# WS2803_7segs_discrete-lightshield3.net
KiCad netlist of a schematic drawn in EAGLE
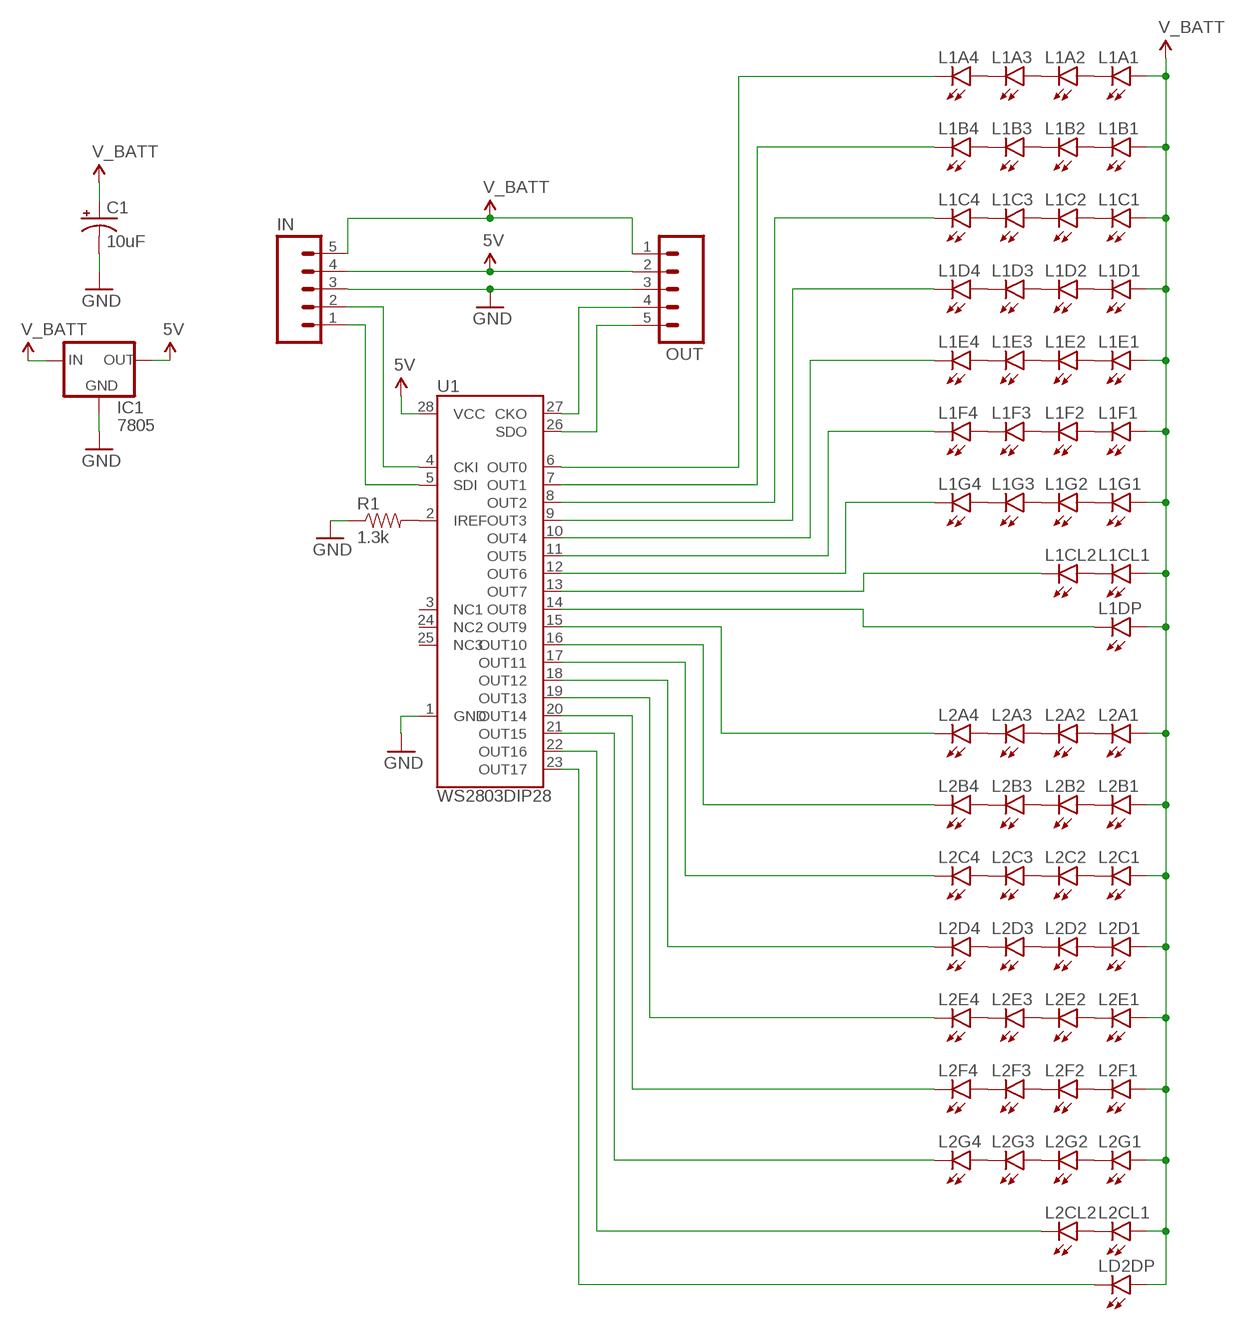
[diagram p0: schematic, sheet 1]

(export (version "E")
  (design (tool "Eeschema 10.0.6"))
  (components
    (comp (ref "C1")
      (value "10uF")
      (footprint "eagle-import:CPOL-RADIAL-10UF-25V")
      (libsource (lib "eagle-import") (part "CAP_POLPTH2"))
    )
    (comp (ref "IC1")
      (value "7805")
      (footprint "eagle-import:TO-92")
      (libsource (lib "eagle-import") (part "V_REG_78XXTO-92_FIXED"))
    )
    (comp (ref "IN")
      (value "M05PTH")
      (footprint "eagle-import:1X05")
      (libsource (lib "eagle-import") (part "M05PTH"))
    )
    (comp (ref "L1A1")
      (value "LED5MM")
      (footprint "eagle-import:LED5MM")
      (libsource (lib "eagle-import") (part "LED5MM"))
    )
    (comp (ref "L1A2")
      (value "LED5MM")
      (footprint "eagle-import:LED5MM")
      (libsource (lib "eagle-import") (part "LED5MM"))
    )
    (comp (ref "L1A3")
      (value "LED5MM")
      (footprint "eagle-import:LED5MM")
      (libsource (lib "eagle-import") (part "LED5MM"))
    )
    (comp (ref "L1A4")
      (value "LED5MM")
      (footprint "eagle-import:LED5MM")
      (libsource (lib "eagle-import") (part "LED5MM"))
    )
    (comp (ref "L1B1")
      (value "LED5MM")
      (footprint "eagle-import:LED5MM")
      (libsource (lib "eagle-import") (part "LED5MM"))
    )
    (comp (ref "L1B2")
      (value "LED5MM")
      (footprint "eagle-import:LED5MM")
      (libsource (lib "eagle-import") (part "LED5MM"))
    )
    (comp (ref "L1B3")
      (value "LED5MM")
      (footprint "eagle-import:LED5MM")
      (libsource (lib "eagle-import") (part "LED5MM"))
    )
    (comp (ref "L1B4")
      (value "LED5MM")
      (footprint "eagle-import:LED5MM")
      (libsource (lib "eagle-import") (part "LED5MM"))
    )
    (comp (ref "L1C1")
      (value "LED5MM")
      (footprint "eagle-import:LED5MM")
      (libsource (lib "eagle-import") (part "LED5MM"))
    )
    (comp (ref "L1C2")
      (value "LED5MM")
      (footprint "eagle-import:LED5MM")
      (libsource (lib "eagle-import") (part "LED5MM"))
    )
    (comp (ref "L1C3")
      (value "LED5MM")
      (footprint "eagle-import:LED5MM")
      (libsource (lib "eagle-import") (part "LED5MM"))
    )
    (comp (ref "L1C4")
      (value "LED5MM")
      (footprint "eagle-import:LED5MM")
      (libsource (lib "eagle-import") (part "LED5MM"))
    )
    (comp (ref "L1CL1")
      (value "LED5MM")
      (footprint "eagle-import:LED5MM")
      (libsource (lib "eagle-import") (part "LED5MM"))
    )
    (comp (ref "L1CL2")
      (value "LED5MM")
      (footprint "eagle-import:LED5MM")
      (libsource (lib "eagle-import") (part "LED5MM"))
    )
    (comp (ref "L1D1")
      (value "LED5MM")
      (footprint "eagle-import:LED5MM")
      (libsource (lib "eagle-import") (part "LED5MM"))
    )
    (comp (ref "L1D2")
      (value "LED5MM")
      (footprint "eagle-import:LED5MM")
      (libsource (lib "eagle-import") (part "LED5MM"))
    )
    (comp (ref "L1D3")
      (value "LED5MM")
      (footprint "eagle-import:LED5MM")
      (libsource (lib "eagle-import") (part "LED5MM"))
    )
    (comp (ref "L1D4")
      (value "LED5MM")
      (footprint "eagle-import:LED5MM")
      (libsource (lib "eagle-import") (part "LED5MM"))
    )
    (comp (ref "L1DP")
      (value "LED5MM")
      (footprint "eagle-import:LED5MM")
      (libsource (lib "eagle-import") (part "LED5MM"))
    )
    (comp (ref "L1E1")
      (value "LED5MM")
      (footprint "eagle-import:LED5MM")
      (libsource (lib "eagle-import") (part "LED5MM"))
    )
    (comp (ref "L1E2")
      (value "LED5MM")
      (footprint "eagle-import:LED5MM")
      (libsource (lib "eagle-import") (part "LED5MM"))
    )
    (comp (ref "L1E3")
      (value "LED5MM")
      (footprint "eagle-import:LED5MM")
      (libsource (lib "eagle-import") (part "LED5MM"))
    )
    (comp (ref "L1E4")
      (value "LED5MM")
      (footprint "eagle-import:LED5MM")
      (libsource (lib "eagle-import") (part "LED5MM"))
    )
    (comp (ref "L1F1")
      (value "LED5MM")
      (footprint "eagle-import:LED5MM")
      (libsource (lib "eagle-import") (part "LED5MM"))
    )
    (comp (ref "L1F2")
      (value "LED5MM")
      (footprint "eagle-import:LED5MM")
      (libsource (lib "eagle-import") (part "LED5MM"))
    )
    (comp (ref "L1F3")
      (value "LED5MM")
      (footprint "eagle-import:LED5MM")
      (libsource (lib "eagle-import") (part "LED5MM"))
    )
    (comp (ref "L1F4")
      (value "LED5MM")
      (footprint "eagle-import:LED5MM")
      (libsource (lib "eagle-import") (part "LED5MM"))
    )
    (comp (ref "L1G1")
      (value "LED5MM")
      (footprint "eagle-import:LED5MM")
      (libsource (lib "eagle-import") (part "LED5MM"))
    )
    (comp (ref "L1G2")
      (value "LED5MM")
      (footprint "eagle-import:LED5MM")
      (libsource (lib "eagle-import") (part "LED5MM"))
    )
    (comp (ref "L1G3")
      (value "LED5MM")
      (footprint "eagle-import:LED5MM")
      (libsource (lib "eagle-import") (part "LED5MM"))
    )
    (comp (ref "L1G4")
      (value "LED5MM")
      (footprint "eagle-import:LED5MM")
      (libsource (lib "eagle-import") (part "LED5MM"))
    )
    (comp (ref "L2A1")
      (value "LED5MM")
      (footprint "eagle-import:LED5MM")
      (libsource (lib "eagle-import") (part "LED5MM"))
    )
    (comp (ref "L2A2")
      (value "LED5MM")
      (footprint "eagle-import:LED5MM")
      (libsource (lib "eagle-import") (part "LED5MM"))
    )
    (comp (ref "L2A3")
      (value "LED5MM")
      (footprint "eagle-import:LED5MM")
      (libsource (lib "eagle-import") (part "LED5MM"))
    )
    (comp (ref "L2A4")
      (value "LED5MM")
      (footprint "eagle-import:LED5MM")
      (libsource (lib "eagle-import") (part "LED5MM"))
    )
    (comp (ref "L2B1")
      (value "LED5MM")
      (footprint "eagle-import:LED5MM")
      (libsource (lib "eagle-import") (part "LED5MM"))
    )
    (comp (ref "L2B2")
      (value "LED5MM")
      (footprint "eagle-import:LED5MM")
      (libsource (lib "eagle-import") (part "LED5MM"))
    )
    (comp (ref "L2B3")
      (value "LED5MM")
      (footprint "eagle-import:LED5MM")
      (libsource (lib "eagle-import") (part "LED5MM"))
    )
    (comp (ref "L2B4")
      (value "LED5MM")
      (footprint "eagle-import:LED5MM")
      (libsource (lib "eagle-import") (part "LED5MM"))
    )
    (comp (ref "L2C1")
      (value "LED5MM")
      (footprint "eagle-import:LED5MM")
      (libsource (lib "eagle-import") (part "LED5MM"))
    )
    (comp (ref "L2C2")
      (value "LED5MM")
      (footprint "eagle-import:LED5MM")
      (libsource (lib "eagle-import") (part "LED5MM"))
    )
    (comp (ref "L2C3")
      (value "LED5MM")
      (footprint "eagle-import:LED5MM")
      (libsource (lib "eagle-import") (part "LED5MM"))
    )
    (comp (ref "L2C4")
      (value "LED5MM")
      (footprint "eagle-import:LED5MM")
      (libsource (lib "eagle-import") (part "LED5MM"))
    )
    (comp (ref "L2CL1")
      (value "LED5MM")
      (footprint "eagle-import:LED5MM")
      (libsource (lib "eagle-import") (part "LED5MM"))
    )
    (comp (ref "L2CL2")
      (value "LED5MM")
      (footprint "eagle-import:LED5MM")
      (libsource (lib "eagle-import") (part "LED5MM"))
    )
    (comp (ref "L2D1")
      (value "LED5MM")
      (footprint "eagle-import:LED5MM")
      (libsource (lib "eagle-import") (part "LED5MM"))
    )
    (comp (ref "L2D2")
      (value "LED5MM")
      (footprint "eagle-import:LED5MM")
      (libsource (lib "eagle-import") (part "LED5MM"))
    )
    (comp (ref "L2D3")
      (value "LED5MM")
      (footprint "eagle-import:LED5MM")
      (libsource (lib "eagle-import") (part "LED5MM"))
    )
    (comp (ref "L2D4")
      (value "LED5MM")
      (footprint "eagle-import:LED5MM")
      (libsource (lib "eagle-import") (part "LED5MM"))
    )
    (comp (ref "L2E1")
      (value "LED5MM")
      (footprint "eagle-import:LED5MM")
      (libsource (lib "eagle-import") (part "LED5MM"))
    )
    (comp (ref "L2E2")
      (value "LED5MM")
      (footprint "eagle-import:LED5MM")
      (libsource (lib "eagle-import") (part "LED5MM"))
    )
    (comp (ref "L2E3")
      (value "LED5MM")
      (footprint "eagle-import:LED5MM")
      (libsource (lib "eagle-import") (part "LED5MM"))
    )
    (comp (ref "L2E4")
      (value "LED5MM")
      (footprint "eagle-import:LED5MM")
      (libsource (lib "eagle-import") (part "LED5MM"))
    )
    (comp (ref "L2F1")
      (value "LED5MM")
      (footprint "eagle-import:LED5MM")
      (libsource (lib "eagle-import") (part "LED5MM"))
    )
    (comp (ref "L2F2")
      (value "LED5MM")
      (footprint "eagle-import:LED5MM")
      (libsource (lib "eagle-import") (part "LED5MM"))
    )
    (comp (ref "L2F3")
      (value "LED5MM")
      (footprint "eagle-import:LED5MM")
      (libsource (lib "eagle-import") (part "LED5MM"))
    )
    (comp (ref "L2F4")
      (value "LED5MM")
      (footprint "eagle-import:LED5MM")
      (libsource (lib "eagle-import") (part "LED5MM"))
    )
    (comp (ref "L2G1")
      (value "LED5MM")
      (footprint "eagle-import:LED5MM")
      (libsource (lib "eagle-import") (part "LED5MM"))
    )
    (comp (ref "L2G2")
      (value "LED5MM")
      (footprint "eagle-import:LED5MM")
      (libsource (lib "eagle-import") (part "LED5MM"))
    )
    (comp (ref "L2G3")
      (value "LED5MM")
      (footprint "eagle-import:LED5MM")
      (libsource (lib "eagle-import") (part "LED5MM"))
    )
    (comp (ref "L2G4")
      (value "LED5MM")
      (footprint "eagle-import:LED5MM")
      (libsource (lib "eagle-import") (part "LED5MM"))
    )
    (comp (ref "LD2DP")
      (value "LED5MM")
      (footprint "eagle-import:LED5MM")
      (libsource (lib "eagle-import") (part "LED5MM"))
    )
    (comp (ref "OUT")
      (value "M05PTH")
      (footprint "eagle-import:1X05")
      (libsource (lib "eagle-import") (part "M05PTH"))
    )
    (comp (ref "R1")
      (value "1.3k")
      (footprint "eagle-import:AXIAL-0.4")
      (libsource (lib "eagle-import") (part "RESISTORPTH-1/4W"))
    )
    (comp (ref "U1")
      (value "WS2803DIP28")
      (footprint "eagle-import:DIP28")
      (libsource (lib "eagle-import") (part "WS2803DIP28"))
    )
  )
  (nets
    (net (code "1") (name "5V") (class "Default")
      (node (ref "IC1") (pin "1") (pinfunction "OUT_1") (pintype "output"))
      (node (ref "IN") (pin "4") (pinfunction "4_4") (pintype "passive"))
      (node (ref "OUT") (pin "2") (pinfunction "2_2") (pintype "passive"))
      (node (ref "U1") (pin "28") (pinfunction "VCC_28") (pintype "bidirectional"))
    )
    (net (code "2") (name "GND") (class "Default")
      (node (ref "C1") (pin "2") (pinfunction "-_2") (pintype "passive"))
      (node (ref "IC1") (pin "2") (pinfunction "GND_2") (pintype "input"))
      (node (ref "IN") (pin "3") (pinfunction "3_3") (pintype "passive"))
      (node (ref "OUT") (pin "3") (pinfunction "3_3") (pintype "passive"))
      (node (ref "R1") (pin "P$1") (pinfunction "1_P$1") (pintype "passive"))
      (node (ref "U1") (pin "1") (pinfunction "GND_1") (pintype "bidirectional"))
    )
    (net (code "3") (name "Net-(L1A1-C)") (class "Default")
      (node (ref "L1A1") (pin "K") (pinfunction "C_K") (pintype "passive"))
      (node (ref "L1A2") (pin "A") (pinfunction "A_A") (pintype "passive"))
    )
    (net (code "4") (name "Net-(L1A2-C)") (class "Default")
      (node (ref "L1A2") (pin "K") (pinfunction "C_K") (pintype "passive"))
      (node (ref "L1A3") (pin "A") (pinfunction "A_A") (pintype "passive"))
    )
    (net (code "5") (name "Net-(L1A3-C)") (class "Default")
      (node (ref "L1A3") (pin "K") (pinfunction "C_K") (pintype "passive"))
      (node (ref "L1A4") (pin "A") (pinfunction "A_A") (pintype "passive"))
    )
    (net (code "6") (name "Net-(L1A4-C)") (class "Default")
      (node (ref "L1A4") (pin "K") (pinfunction "C_K") (pintype "passive"))
      (node (ref "U1") (pin "6") (pinfunction "OUT0_6") (pintype "bidirectional"))
    )
    (net (code "7") (name "Net-(L1B1-C)") (class "Default")
      (node (ref "L1B1") (pin "K") (pinfunction "C_K") (pintype "passive"))
      (node (ref "L1B2") (pin "A") (pinfunction "A_A") (pintype "passive"))
    )
    (net (code "8") (name "Net-(L1B2-C)") (class "Default")
      (node (ref "L1B2") (pin "K") (pinfunction "C_K") (pintype "passive"))
      (node (ref "L1B3") (pin "A") (pinfunction "A_A") (pintype "passive"))
    )
    (net (code "9") (name "Net-(L1B3-C)") (class "Default")
      (node (ref "L1B3") (pin "K") (pinfunction "C_K") (pintype "passive"))
      (node (ref "L1B4") (pin "A") (pinfunction "A_A") (pintype "passive"))
    )
    (net (code "10") (name "Net-(L1B4-C)") (class "Default")
      (node (ref "L1B4") (pin "K") (pinfunction "C_K") (pintype "passive"))
      (node (ref "U1") (pin "7") (pinfunction "OUT1_7") (pintype "bidirectional"))
    )
    (net (code "11") (name "Net-(L1C1-C)") (class "Default")
      (node (ref "L1C1") (pin "K") (pinfunction "C_K") (pintype "passive"))
      (node (ref "L1C2") (pin "A") (pinfunction "A_A") (pintype "passive"))
    )
    (net (code "12") (name "Net-(L1C2-C)") (class "Default")
      (node (ref "L1C2") (pin "K") (pinfunction "C_K") (pintype "passive"))
      (node (ref "L1C3") (pin "A") (pinfunction "A_A") (pintype "passive"))
    )
    (net (code "13") (name "Net-(L1C3-C)") (class "Default")
      (node (ref "L1C3") (pin "K") (pinfunction "C_K") (pintype "passive"))
      (node (ref "L1C4") (pin "A") (pinfunction "A_A") (pintype "passive"))
    )
    (net (code "14") (name "Net-(L1C4-C)") (class "Default")
      (node (ref "L1C4") (pin "K") (pinfunction "C_K") (pintype "passive"))
      (node (ref "U1") (pin "8") (pinfunction "OUT2_8") (pintype "bidirectional"))
    )
    (net (code "15") (name "Net-(L1CL1-C)") (class "Default")
      (node (ref "L1CL1") (pin "K") (pinfunction "C_K") (pintype "passive"))
      (node (ref "L1CL2") (pin "A") (pinfunction "A_A") (pintype "passive"))
    )
    (net (code "16") (name "Net-(L1CL2-C)") (class "Default")
      (node (ref "L1CL2") (pin "K") (pinfunction "C_K") (pintype "passive"))
      (node (ref "U1") (pin "13") (pinfunction "OUT7_13") (pintype "bidirectional"))
    )
    (net (code "17") (name "Net-(L1D1-C)") (class "Default")
      (node (ref "L1D1") (pin "K") (pinfunction "C_K") (pintype "passive"))
      (node (ref "L1D2") (pin "A") (pinfunction "A_A") (pintype "passive"))
    )
    (net (code "18") (name "Net-(L1D2-C)") (class "Default")
      (node (ref "L1D2") (pin "K") (pinfunction "C_K") (pintype "passive"))
      (node (ref "L1D3") (pin "A") (pinfunction "A_A") (pintype "passive"))
    )
    (net (code "19") (name "Net-(L1D3-C)") (class "Default")
      (node (ref "L1D3") (pin "K") (pinfunction "C_K") (pintype "passive"))
      (node (ref "L1D4") (pin "A") (pinfunction "A_A") (pintype "passive"))
    )
    (net (code "20") (name "Net-(L1D4-C)") (class "Default")
      (node (ref "L1D4") (pin "K") (pinfunction "C_K") (pintype "passive"))
      (node (ref "U1") (pin "9") (pinfunction "OUT3_9") (pintype "bidirectional"))
    )
    (net (code "21") (name "Net-(L1DP-C)") (class "Default")
      (node (ref "L1DP") (pin "K") (pinfunction "C_K") (pintype "passive"))
      (node (ref "U1") (pin "14") (pinfunction "OUT8_14") (pintype "bidirectional"))
    )
    (net (code "22") (name "Net-(L1E1-C)") (class "Default")
      (node (ref "L1E1") (pin "K") (pinfunction "C_K") (pintype "passive"))
      (node (ref "L1E2") (pin "A") (pinfunction "A_A") (pintype "passive"))
    )
    (net (code "23") (name "Net-(L1E2-C)") (class "Default")
      (node (ref "L1E2") (pin "K") (pinfunction "C_K") (pintype "passive"))
      (node (ref "L1E3") (pin "A") (pinfunction "A_A") (pintype "passive"))
    )
    (net (code "24") (name "Net-(L1E3-C)") (class "Default")
      (node (ref "L1E3") (pin "K") (pinfunction "C_K") (pintype "passive"))
      (node (ref "L1E4") (pin "A") (pinfunction "A_A") (pintype "passive"))
    )
    (net (code "25") (name "Net-(L1E4-C)") (class "Default")
      (node (ref "L1E4") (pin "K") (pinfunction "C_K") (pintype "passive"))
      (node (ref "U1") (pin "10") (pinfunction "OUT4_10") (pintype "bidirectional"))
    )
    (net (code "26") (name "Net-(L1F1-C)") (class "Default")
      (node (ref "L1F1") (pin "K") (pinfunction "C_K") (pintype "passive"))
      (node (ref "L1F2") (pin "A") (pinfunction "A_A") (pintype "passive"))
    )
    (net (code "27") (name "Net-(L1F2-C)") (class "Default")
      (node (ref "L1F2") (pin "K") (pinfunction "C_K") (pintype "passive"))
      (node (ref "L1F3") (pin "A") (pinfunction "A_A") (pintype "passive"))
    )
    (net (code "28") (name "Net-(L1F3-C)") (class "Default")
      (node (ref "L1F3") (pin "K") (pinfunction "C_K") (pintype "passive"))
      (node (ref "L1F4") (pin "A") (pinfunction "A_A") (pintype "passive"))
    )
    (net (code "29") (name "Net-(L1F4-C)") (class "Default")
      (node (ref "L1F4") (pin "K") (pinfunction "C_K") (pintype "passive"))
      (node (ref "U1") (pin "11") (pinfunction "OUT5_11") (pintype "bidirectional"))
    )
    (net (code "30") (name "Net-(L1G1-C)") (class "Default")
      (node (ref "L1G1") (pin "K") (pinfunction "C_K") (pintype "passive"))
      (node (ref "L1G2") (pin "A") (pinfunction "A_A") (pintype "passive"))
    )
    (net (code "31") (name "Net-(L1G2-C)") (class "Default")
      (node (ref "L1G2") (pin "K") (pinfunction "C_K") (pintype "passive"))
      (node (ref "L1G3") (pin "A") (pinfunction "A_A") (pintype "passive"))
    )
    (net (code "32") (name "Net-(L1G3-C)") (class "Default")
      (node (ref "L1G3") (pin "K") (pinfunction "C_K") (pintype "passive"))
      (node (ref "L1G4") (pin "A") (pinfunction "A_A") (pintype "passive"))
    )
    (net (code "33") (name "Net-(L1G4-C)") (class "Default")
      (node (ref "L1G4") (pin "K") (pinfunction "C_K") (pintype "passive"))
      (node (ref "U1") (pin "12") (pinfunction "OUT6_12") (pintype "bidirectional"))
    )
    (net (code "34") (name "Net-(L2A1-C)") (class "Default")
      (node (ref "L2A1") (pin "K") (pinfunction "C_K") (pintype "passive"))
      (node (ref "L2A2") (pin "A") (pinfunction "A_A") (pintype "passive"))
    )
    (net (code "35") (name "Net-(L2A2-C)") (class "Default")
      (node (ref "L2A2") (pin "K") (pinfunction "C_K") (pintype "passive"))
      (node (ref "L2A3") (pin "A") (pinfunction "A_A") (pintype "passive"))
    )
    (net (code "36") (name "Net-(L2A3-C)") (class "Default")
      (node (ref "L2A3") (pin "K") (pinfunction "C_K") (pintype "passive"))
      (node (ref "L2A4") (pin "A") (pinfunction "A_A") (pintype "passive"))
    )
    (net (code "37") (name "Net-(L2A4-C)") (class "Default")
      (node (ref "L2A4") (pin "K") (pinfunction "C_K") (pintype "passive"))
      (node (ref "U1") (pin "15") (pinfunction "OUT9_15") (pintype "bidirectional"))
    )
    (net (code "38") (name "Net-(L2B1-C)") (class "Default")
      (node (ref "L2B1") (pin "K") (pinfunction "C_K") (pintype "passive"))
      (node (ref "L2B2") (pin "A") (pinfunction "A_A") (pintype "passive"))
    )
    (net (code "39") (name "Net-(L2B2-C)") (class "Default")
      (node (ref "L2B2") (pin "K") (pinfunction "C_K") (pintype "passive"))
      (node (ref "L2B3") (pin "A") (pinfunction "A_A") (pintype "passive"))
    )
    (net (code "40") (name "Net-(L2B3-C)") (class "Default")
      (node (ref "L2B3") (pin "K") (pinfunction "C_K") (pintype "passive"))
      (node (ref "L2B4") (pin "A") (pinfunction "A_A") (pintype "passive"))
    )
    (net (code "41") (name "Net-(L2B4-C)") (class "Default")
      (node (ref "L2B4") (pin "K") (pinfunction "C_K") (pintype "passive"))
      (node (ref "U1") (pin "16") (pinfunction "OUT10_16") (pintype "bidirectional"))
    )
    (net (code "42") (name "Net-(L2C1-C)") (class "Default")
      (node (ref "L2C1") (pin "K") (pinfunction "C_K") (pintype "passive"))
      (node (ref "L2C2") (pin "A") (pinfunction "A_A") (pintype "passive"))
    )
    (net (code "43") (name "Net-(L2C2-C)") (class "Default")
      (node (ref "L2C2") (pin "K") (pinfunction "C_K") (pintype "passive"))
      (node (ref "L2C3") (pin "A") (pinfunction "A_A") (pintype "passive"))
    )
    (net (code "44") (name "Net-(L2C3-C)") (class "Default")
      (node (ref "L2C3") (pin "K") (pinfunction "C_K") (pintype "passive"))
      (node (ref "L2C4") (pin "A") (pinfunction "A_A") (pintype "passive"))
    )
    (net (code "45") (name "Net-(L2C4-C)") (class "Default")
      (node (ref "L2C4") (pin "K") (pinfunction "C_K") (pintype "passive"))
      (node (ref "U1") (pin "17") (pinfunction "OUT11_17") (pintype "bidirectional"))
    )
    (net (code "46") (name "Net-(L2CL1-C)") (class "Default")
      (node (ref "L2CL1") (pin "K") (pinfunction "C_K") (pintype "passive"))
      (node (ref "L2CL2") (pin "A") (pinfunction "A_A") (pintype "passive"))
    )
    (net (code "47") (name "Net-(L2CL2-C)") (class "Default")
      (node (ref "L2CL2") (pin "K") (pinfunction "C_K") (pintype "passive"))
      (node (ref "U1") (pin "22") (pinfunction "OUT16_22") (pintype "bidirectional"))
    )
    (net (code "48") (name "Net-(L2D1-C)") (class "Default")
      (node (ref "L2D1") (pin "K") (pinfunction "C_K") (pintype "passive"))
      (node (ref "L2D2") (pin "A") (pinfunction "A_A") (pintype "passive"))
    )
    (net (code "49") (name "Net-(L2D2-C)") (class "Default")
      (node (ref "L2D2") (pin "K") (pinfunction "C_K") (pintype "passive"))
      (node (ref "L2D3") (pin "A") (pinfunction "A_A") (pintype "passive"))
    )
    (net (code "50") (name "Net-(L2D3-C)") (class "Default")
      (node (ref "L2D3") (pin "K") (pinfunction "C_K") (pintype "passive"))
      (node (ref "L2D4") (pin "A") (pinfunction "A_A") (pintype "passive"))
    )
    (net (code "51") (name "Net-(L2D4-C)") (class "Default")
      (node (ref "L2D4") (pin "K") (pinfunction "C_K") (pintype "passive"))
      (node (ref "U1") (pin "18") (pinfunction "OUT12_18") (pintype "bidirectional"))
    )
    (net (code "52") (name "Net-(L2E1-C)") (class "Default")
      (node (ref "L2E1") (pin "K") (pinfunction "C_K") (pintype "passive"))
      (node (ref "L2E2") (pin "A") (pinfunction "A_A") (pintype "passive"))
    )
    (net (code "53") (name "Net-(L2E2-C)") (class "Default")
      (node (ref "L2E2") (pin "K") (pinfunction "C_K") (pintype "passive"))
      (node (ref "L2E3") (pin "A") (pinfunction "A_A") (pintype "passive"))
    )
    (net (code "54") (name "Net-(L2E3-C)") (class "Default")
      (node (ref "L2E3") (pin "K") (pinfunction "C_K") (pintype "passive"))
      (node (ref "L2E4") (pin "A") (pinfunction "A_A") (pintype "passive"))
    )
    (net (code "55") (name "Net-(L2E4-C)") (class "Default")
      (node (ref "L2E4") (pin "K") (pinfunction "C_K") (pintype "passive"))
      (node (ref "U1") (pin "19") (pinfunction "OUT13_19") (pintype "bidirectional"))
    )
    (net (code "56") (name "Net-(L2F1-C)") (class "Default")
      (node (ref "L2F1") (pin "K") (pinfunction "C_K") (pintype "passive"))
      (node (ref "L2F2") (pin "A") (pinfunction "A_A") (pintype "passive"))
    )
    (net (code "57") (name "Net-(L2F2-C)") (class "Default")
      (node (ref "L2F2") (pin "K") (pinfunction "C_K") (pintype "passive"))
      (node (ref "L2F3") (pin "A") (pinfunction "A_A") (pintype "passive"))
    )
    (net (code "58") (name "Net-(L2F3-C)") (class "Default")
      (node (ref "L2F3") (pin "K") (pinfunction "C_K") (pintype "passive"))
      (node (ref "L2F4") (pin "A") (pinfunction "A_A") (pintype "passive"))
    )
    (net (code "59") (name "Net-(L2F4-C)") (class "Default")
      (node (ref "L2F4") (pin "K") (pinfunction "C_K") (pintype "passive"))
      (node (ref "U1") (pin "20") (pinfunction "OUT14_20") (pintype "bidirectional"))
    )
    (net (code "60") (name "Net-(L2G1-C)") (class "Default")
      (node (ref "L2G1") (pin "K") (pinfunction "C_K") (pintype "passive"))
      (node (ref "L2G2") (pin "A") (pinfunction "A_A") (pintype "passive"))
    )
    (net (code "61") (name "Net-(L2G2-C)") (class "Default")
      (node (ref "L2G2") (pin "K") (pinfunction "C_K") (pintype "passive"))
      (node (ref "L2G3") (pin "A") (pinfunction "A_A") (pintype "passive"))
    )
    (net (code "62") (name "Net-(L2G3-C)") (class "Default")
      (node (ref "L2G3") (pin "K") (pinfunction "C_K") (pintype "passive"))
      (node (ref "L2G4") (pin "A") (pinfunction "A_A") (pintype "passive"))
    )
    (net (code "63") (name "Net-(L2G4-C)") (class "Default")
      (node (ref "L2G4") (pin "K") (pinfunction "C_K") (pintype "passive"))
      (node (ref "U1") (pin "21") (pinfunction "OUT15_21") (pintype "bidirectional"))
    )
    (net (code "64") (name "Net-(LD2DP-C)") (class "Default")
      (node (ref "LD2DP") (pin "K") (pinfunction "C_K") (pintype "passive"))
      (node (ref "U1") (pin "23") (pinfunction "OUT17_23") (pintype "bidirectional"))
    )
    (net (code "65") (name "Net-(R1-2)") (class "Default")
      (node (ref "R1") (pin "P$2") (pinfunction "2_P$2") (pintype "passive"))
      (node (ref "U1") (pin "2") (pinfunction "IREF_2") (pintype "bidirectional"))
    )
    (net (code "66") (name "Net-(U1-CKI)") (class "Default")
      (node (ref "IN") (pin "2") (pinfunction "2_2") (pintype "passive"))
      (node (ref "U1") (pin "4") (pinfunction "CKI_4") (pintype "bidirectional"))
    )
    (net (code "67") (name "Net-(U1-CKO)") (class "Default")
      (node (ref "OUT") (pin "4") (pinfunction "4_4") (pintype "passive"))
      (node (ref "U1") (pin "27") (pinfunction "CKO_27") (pintype "bidirectional"))
    )
    (net (code "68") (name "Net-(U1-SDI)") (class "Default")
      (node (ref "IN") (pin "1") (pinfunction "1_1") (pintype "passive"))
      (node (ref "U1") (pin "5") (pinfunction "SDI_5") (pintype "bidirectional"))
    )
    (net (code "69") (name "Net-(U1-SDO)") (class "Default")
      (node (ref "OUT") (pin "5") (pinfunction "5_5") (pintype "passive"))
      (node (ref "U1") (pin "26") (pinfunction "SDO_26") (pintype "bidirectional"))
    )
    (net (code "70") (name "V_BATT") (class "Default")
      (node (ref "C1") (pin "1") (pinfunction "+_1") (pintype "passive"))
      (node (ref "IC1") (pin "3") (pinfunction "IN_3") (pintype "input"))
      (node (ref "IN") (pin "5") (pinfunction "5_5") (pintype "passive"))
      (node (ref "L1A1") (pin "A") (pinfunction "A_A") (pintype "passive"))
      (node (ref "L1B1") (pin "A") (pinfunction "A_A") (pintype "passive"))
      (node (ref "L1C1") (pin "A") (pinfunction "A_A") (pintype "passive"))
      (node (ref "L1CL1") (pin "A") (pinfunction "A_A") (pintype "passive"))
      (node (ref "L1D1") (pin "A") (pinfunction "A_A") (pintype "passive"))
      (node (ref "L1DP") (pin "A") (pinfunction "A_A") (pintype "passive"))
      (node (ref "L1E1") (pin "A") (pinfunction "A_A") (pintype "passive"))
      (node (ref "L1F1") (pin "A") (pinfunction "A_A") (pintype "passive"))
      (node (ref "L1G1") (pin "A") (pinfunction "A_A") (pintype "passive"))
      (node (ref "L2A1") (pin "A") (pinfunction "A_A") (pintype "passive"))
      (node (ref "L2B1") (pin "A") (pinfunction "A_A") (pintype "passive"))
      (node (ref "L2C1") (pin "A") (pinfunction "A_A") (pintype "passive"))
      (node (ref "L2CL1") (pin "A") (pinfunction "A_A") (pintype "passive"))
      (node (ref "L2D1") (pin "A") (pinfunction "A_A") (pintype "passive"))
      (node (ref "L2E1") (pin "A") (pinfunction "A_A") (pintype "passive"))
      (node (ref "L2F1") (pin "A") (pinfunction "A_A") (pintype "passive"))
      (node (ref "L2G1") (pin "A") (pinfunction "A_A") (pintype "passive"))
      (node (ref "LD2DP") (pin "A") (pinfunction "A_A") (pintype "passive"))
      (node (ref "OUT") (pin "1") (pinfunction "1_1") (pintype "passive"))
    )
    (net (code "71") (name "unconnected-(U1-NC1-Pad3)") (class "Default")
      (node (ref "U1") (pin "3") (pinfunction "NC1_3") (pintype "bidirectional"))
    )
    (net (code "72") (name "unconnected-(U1-NC2-Pad24)") (class "Default")
      (node (ref "U1") (pin "24") (pinfunction "NC2_24") (pintype "bidirectional"))
    )
    (net (code "73") (name "unconnected-(U1-NC3-Pad25)") (class "Default")
      (node (ref "U1") (pin "25") (pinfunction "NC3_25") (pintype "bidirectional"))
    )
  )
)
